# power_stage.net
KiCad netlist of a schematic drawn in Altium Designer
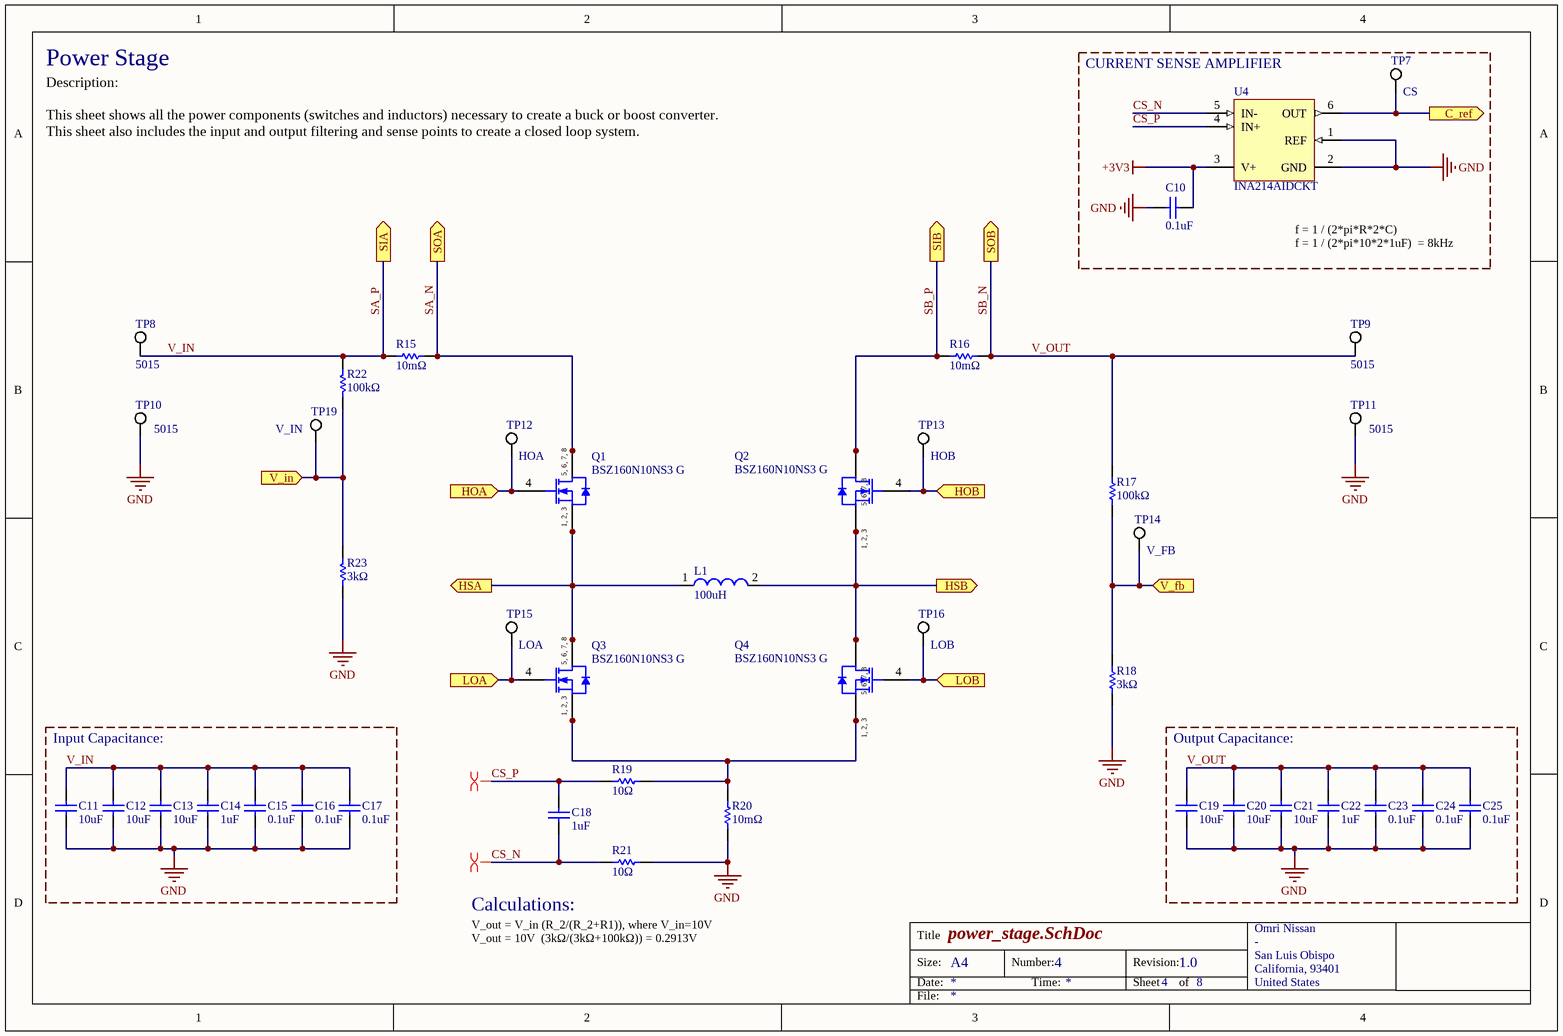
[diagram p0: power_stage.SchDoc]

(export (version "E")
  (design (tool "Eeschema 10.0.6"))
  (components
    (comp (ref "C10")
      (value "0.1uF")
      (footprint "CAPC1608X90X35ML10T15")
      (fields
        (field (name "TOLERANCE") "10%")
        (field (name "VOLTAGE") "50V")
        (field (name "MANUFACTURER") "Murata")
      )
      (libsource (lib "Altium Content Vault") (part "CAP-NP-2"))
    )
    (comp (ref "C11")
      (value "10uF")
      (footprint "CAPC3216X180X20LL20")
      (fields
        (field (name "MANUFACTURER") "TDK")
        (field (name "PCN PART NUMBER") "MLCCPartNumberChange30/Nov/2012")
        (field (name "TOLERANCE") "±10%")
      )
      (libsource (lib "Altium Content Vault") (part "CAP-NP-2"))
    )
    (comp (ref "C12")
      (value "10uF")
      (footprint "CAPC3216X180X20LL20")
      (fields
        (field (name "MANUFACTURER") "TDK")
        (field (name "PCN PART NUMBER") "MLCCPartNumberChange30/Nov/2012")
        (field (name "TOLERANCE") "±10%")
      )
      (libsource (lib "Altium Content Vault") (part "CAP-NP-2"))
    )
    (comp (ref "C13")
      (value "10uF")
      (footprint "CAPC3216X180X20LL20")
      (fields
        (field (name "MANUFACTURER") "TDK")
        (field (name "PCN PART NUMBER") "MLCCPartNumberChange30/Nov/2012")
        (field (name "TOLERANCE") "±10%")
      )
      (libsource (lib "Altium Content Vault") (part "CAP-NP-2"))
    )
    (comp (ref "C14")
      (value "1uF")
      (footprint "CAPC1608X90X20LL10")
      (fields
        (field (name "MANUFACTURER") "TDK")
        (field (name "PCN PART NUMBER") "MLCCPartNumberChange30/Nov/2012")
        (field (name "TOLERANCE") "±10%")
      )
      (libsource (lib "Altium Content Vault") (part "CAP-NP-2"))
    )
    (comp (ref "C15")
      (value "0.1uF")
      (footprint "CAPC1608X90X35ML10T15")
      (fields
        (field (name "TOLERANCE") "10%")
        (field (name "VOLTAGE") "50V")
        (field (name "MANUFACTURER") "Murata")
      )
      (libsource (lib "Altium Content Vault") (part "CAP-NP-2"))
    )
    (comp (ref "C16")
      (value "0.1uF")
      (footprint "CAPC1608X90X35ML10T15")
      (fields
        (field (name "TOLERANCE") "10%")
        (field (name "VOLTAGE") "50V")
        (field (name "MANUFACTURER") "Murata")
      )
      (libsource (lib "Altium Content Vault") (part "CAP-NP-2"))
    )
    (comp (ref "C17")
      (value "0.1uF")
      (footprint "CAPC1608X90X35ML10T15")
      (fields
        (field (name "TOLERANCE") "10%")
        (field (name "VOLTAGE") "50V")
        (field (name "MANUFACTURER") "Murata")
      )
      (libsource (lib "Altium Content Vault") (part "CAP-NP-2"))
    )
    (comp (ref "C18")
      (value "1uF")
      (footprint "CAPC1608X90X20LL10")
      (fields
        (field (name "MANUFACTURER") "TDK")
        (field (name "PCN PART NUMBER") "MLCCPartNumberChange30/Nov/2012")
        (field (name "TOLERANCE") "±10%")
      )
      (libsource (lib "Altium Content Vault") (part "CAP-NP-2"))
    )
    (comp (ref "C19")
      (value "10uF")
      (footprint "CAPC3216X180X20LL20")
      (fields
        (field (name "MANUFACTURER") "TDK")
        (field (name "PCN PART NUMBER") "MLCCPartNumberChange30/Nov/2012")
        (field (name "TOLERANCE") "±10%")
      )
      (libsource (lib "Altium Content Vault") (part "CAP-NP-2"))
    )
    (comp (ref "C20")
      (value "10uF")
      (footprint "CAPC3216X180X20LL20")
      (fields
        (field (name "MANUFACTURER") "TDK")
        (field (name "PCN PART NUMBER") "MLCCPartNumberChange30/Nov/2012")
        (field (name "TOLERANCE") "±10%")
      )
      (libsource (lib "Altium Content Vault") (part "CAP-NP-2"))
    )
    (comp (ref "C21")
      (value "10uF")
      (footprint "CAPC3216X180X20LL20")
      (fields
        (field (name "MANUFACTURER") "TDK")
        (field (name "PCN PART NUMBER") "MLCCPartNumberChange30/Nov/2012")
        (field (name "TOLERANCE") "±10%")
      )
      (libsource (lib "Altium Content Vault") (part "CAP-NP-2"))
    )
    (comp (ref "C22")
      (value "1uF")
      (footprint "CAPC1608X90X20LL10")
      (fields
        (field (name "MANUFACTURER") "TDK")
        (field (name "PCN PART NUMBER") "MLCCPartNumberChange30/Nov/2012")
        (field (name "TOLERANCE") "±10%")
      )
      (libsource (lib "Altium Content Vault") (part "CAP-NP-2"))
    )
    (comp (ref "C23")
      (value "0.1uF")
      (footprint "CAPC1608X90X35ML10T15")
      (fields
        (field (name "TOLERANCE") "10%")
        (field (name "VOLTAGE") "50V")
        (field (name "MANUFACTURER") "Murata")
      )
      (libsource (lib "Altium Content Vault") (part "CAP-NP-2"))
    )
    (comp (ref "C24")
      (value "0.1uF")
      (footprint "CAPC1608X90X35ML10T15")
      (fields
        (field (name "TOLERANCE") "10%")
        (field (name "VOLTAGE") "50V")
        (field (name "MANUFACTURER") "Murata")
      )
      (libsource (lib "Altium Content Vault") (part "CAP-NP-2"))
    )
    (comp (ref "C25")
      (value "0.1uF")
      (footprint "CAPC1608X90X35ML10T15")
      (fields
        (field (name "TOLERANCE") "10%")
        (field (name "VOLTAGE") "50V")
        (field (name "MANUFACTURER") "Murata")
      )
      (libsource (lib "Altium Content Vault") (part "CAP-NP-2"))
    )
    (comp (ref "L1")
      (value "100uH")
      (footprint "WE-PD-XXL")
      (description "7447709101 - SMD-Shielded Power Inductor WE-PD, L = 100 µH")
      (libsource (lib "Altium Content Vault") (part "PAS-IND-INDUCTOR-2"))
    )
    (comp (ref "Q1")
      (value "BSZ160N10NS3 G")
      (footprint "INF-PG-TSDSON-8-1_V")
      (fields (field (name "MANUFACTURER") "Infineon"))
      (libsource (lib "Altium Content Vault") (part "INF-NEMOS-SSSGDDDD-8"))
    )
    (comp (ref "Q2")
      (value "BSZ160N10NS3 G")
      (footprint "INF-PG-TSDSON-8-1_V")
      (fields (field (name "MANUFACTURER") "Infineon"))
      (libsource (lib "Altium Content Vault") (part "INF-NEMOS-SSSGDDDD-8"))
    )
    (comp (ref "Q3")
      (value "BSZ160N10NS3 G")
      (footprint "INF-PG-TSDSON-8-1_V")
      (fields (field (name "MANUFACTURER") "Infineon"))
      (libsource (lib "Altium Content Vault") (part "INF-NEMOS-SSSGDDDD-8"))
    )
    (comp (ref "Q4")
      (value "BSZ160N10NS3 G")
      (footprint "INF-PG-TSDSON-8-1_V")
      (fields (field (name "MANUFACTURER") "Infineon"))
      (libsource (lib "Altium Content Vault") (part "INF-NEMOS-SSSGDDDD-8"))
    )
    (comp (ref "R15")
      (value "10mΩ")
      (footprint "RESC3216X70X50NL05T20")
      (description "ERJ8CWFR010V")
      (fields (field (name "MANUFACTURER") "Panasonic"))
      (libsource (lib "Altium Content Vault") (part "RES"))
    )
    (comp (ref "R16")
      (value "10mΩ")
      (footprint "RESC3216X70X50NL05T20")
      (description "ERJ8CWFR010V")
      (fields (field (name "MANUFACTURER") "Panasonic"))
      (libsource (lib "Altium Content Vault") (part "RES"))
    )
    (comp (ref "R17")
      (value "100kΩ")
      (footprint "RESC1608X55X30ML20T20")
      (description "ERA3AEB104V")
      (fields (field (name "MANUFACTURER") "Panasonic"))
      (libsource (lib "Altium Content Vault") (part "RES"))
    )
    (comp (ref "R18")
      (value "3kΩ")
      (footprint "RESC1608X55X25ML10T15")
      (description "RT0603BRD073KL")
      (fields (field (name "MANUFACTURER") "Yageo"))
      (libsource (lib "Altium Content Vault") (part "RES"))
    )
    (comp (ref "R19")
      (value "10Ω")
      (footprint "RESC1609X50X30NL10T20")
      (description "CRCW060310R0JNEA")
      (fields (field (name "MANUFACTURER") "Vishay Dale"))
      (libsource (lib "Altium Content Vault") (part "RES"))
    )
    (comp (ref "R20")
      (value "10mΩ")
      (footprint "RESC3216X70X50NL05T20")
      (description "ERJ8CWFR010V")
      (fields (field (name "MANUFACTURER") "Panasonic"))
      (libsource (lib "Altium Content Vault") (part "RES"))
    )
    (comp (ref "R21")
      (value "10Ω")
      (footprint "RESC1609X50X30NL10T20")
      (description "CRCW060310R0JNEA")
      (fields (field (name "MANUFACTURER") "Vishay Dale"))
      (libsource (lib "Altium Content Vault") (part "RES"))
    )
    (comp (ref "R22")
      (value "100kΩ")
      (footprint "RESC1608X55X30ML20T20")
      (description "ERA3AEB104V")
      (fields (field (name "MANUFACTURER") "Panasonic"))
      (libsource (lib "Altium Content Vault") (part "RES"))
    )
    (comp (ref "R23")
      (value "3kΩ")
      (footprint "RESC1608X55X25ML10T15")
      (description "RT0603BRD073KL")
      (fields (field (name "MANUFACTURER") "Yageo"))
      (libsource (lib "Altium Content Vault") (part "RES"))
    )
    (comp (ref "TP7")
      (value "CS")
      (footprint "KSTN-5012_V")
      (description "Test Point, White, Through Hole, RoHS, Bulk")
      (fields (field (name "MANUFACTURER") "Keystone"))
      (libsource (lib "Altium Content Vault") (part "TESTPOINT_WHITE"))
    )
    (comp (ref "TP8")
      (value "5015")
      (footprint "KSTN-5015_V")
      (description "Test Point, White, SMT")
      (fields (field (name "MANUFACTURER") "Keystone"))
      (libsource (lib "Altium Content Vault") (part "TESTPOINT_WHITE"))
    )
    (comp (ref "TP9")
      (value "5015")
      (footprint "KSTN-5015_V")
      (description "Test Point, White, SMT")
      (fields (field (name "MANUFACTURER") "Keystone"))
      (libsource (lib "Altium Content Vault") (part "TESTPOINT_WHITE"))
    )
    (comp (ref "TP10")
      (value "5015")
      (footprint "KSTN-5015_V")
      (description "Test Point, White, SMT")
      (fields (field (name "MANUFACTURER") "Keystone"))
      (libsource (lib "Altium Content Vault") (part "TESTPOINT_WHITE"))
    )
    (comp (ref "TP11")
      (value "5015")
      (footprint "KSTN-5015_V")
      (description "Test Point, White, SMT")
      (fields (field (name "MANUFACTURER") "Keystone"))
      (libsource (lib "Altium Content Vault") (part "TESTPOINT_WHITE"))
    )
    (comp (ref "TP12")
      (value "HOA")
      (footprint "KSTN-5012_V")
      (description "Test Point, White, Through Hole, RoHS, Bulk")
      (fields (field (name "MANUFACTURER") "Keystone"))
      (libsource (lib "Altium Content Vault") (part "TESTPOINT_WHITE"))
    )
    (comp (ref "TP13")
      (value "HOB")
      (footprint "KSTN-5012_V")
      (description "Test Point, White, Through Hole, RoHS, Bulk")
      (fields (field (name "MANUFACTURER") "Keystone"))
      (libsource (lib "Altium Content Vault") (part "TESTPOINT_WHITE"))
    )
    (comp (ref "TP14")
      (value "V_FB")
      (footprint "KSTN-5012_V")
      (description "Test Point, White, Through Hole, RoHS, Bulk")
      (fields (field (name "MANUFACTURER") "Keystone"))
      (libsource (lib "Altium Content Vault") (part "TESTPOINT_WHITE"))
    )
    (comp (ref "TP15")
      (value "LOA")
      (footprint "KSTN-5012_V")
      (description "Test Point, White, Through Hole, RoHS, Bulk")
      (fields (field (name "MANUFACTURER") "Keystone"))
      (libsource (lib "Altium Content Vault") (part "TESTPOINT_WHITE"))
    )
    (comp (ref "TP16")
      (value "LOB")
      (footprint "KSTN-5012_V")
      (description "Test Point, White, Through Hole, RoHS, Bulk")
      (fields (field (name "MANUFACTURER") "Keystone"))
      (libsource (lib "Altium Content Vault") (part "TESTPOINT_WHITE"))
    )
    (comp (ref "TP19")
      (value "V_IN")
      (footprint "KSTN-5012_V")
      (description "Test Point, White, Through Hole, RoHS, Bulk")
      (fields (field (name "MANUFACTURER") "Keystone"))
      (libsource (lib "Altium Content Vault") (part "TESTPOINT_WHITE"))
    )
    (comp (ref "U4")
      (value "INA214AIDCKT")
      (footprint "DCK0006A_L")
      (fields (field (name "MANUFACTURER") "TexasInstruments"))
      (libsource (lib "Altium Content Vault") (part "TI-INA21X_199A-DCK-6"))
    )
  )
  (nets
    (net (code "1") (name "+3V3") (class "Default")
      (node (ref "C10") (pin "1") (pinfunction "1_1") (pintype "passive"))
      (node (ref "U4") (pin "3") (pinfunction "V+_3") (pintype "power_in"))
    )
    (net (code "2") (name "/CS_N") (class "Default")
      (node (ref "C18") (pin "2") (pinfunction "2_2") (pintype "passive"))
      (node (ref "R21") (pin "1") (pinfunction "1_1") (pintype "passive"))
      (node (ref "U4") (pin "5") (pinfunction "IN-_5") (pintype "input"))
    )
    (net (code "3") (name "/CS_P") (class "Default")
      (node (ref "C18") (pin "1") (pinfunction "1_1") (pintype "passive"))
      (node (ref "R19") (pin "1") (pinfunction "1_1") (pintype "passive"))
      (node (ref "U4") (pin "4") (pinfunction "IN+_4") (pintype "input"))
    )
    (net (code "4") (name "/C_ref") (class "Default")
      (node (ref "TP7") (pin "1") (pinfunction "1_1") (pintype "passive"))
      (node (ref "U4") (pin "6") (pinfunction "OUT_6") (pintype "output"))
    )
    (net (code "5") (name "/HOA") (class "Default")
      (node (ref "Q1") (pin "4") (pinfunction "GATE_4") (pintype "passive"))
      (node (ref "TP12") (pin "1") (pinfunction "1_1") (pintype "passive"))
    )
    (net (code "6") (name "/HOB") (class "Default")
      (node (ref "Q2") (pin "4") (pinfunction "GATE_4") (pintype "passive"))
      (node (ref "TP13") (pin "1") (pinfunction "1_1") (pintype "passive"))
    )
    (net (code "7") (name "/HSA") (class "Default")
      (node (ref "L1") (pin "1") (pinfunction "1_1") (pintype "passive"))
      (node (ref "Q1") (pin "1") (pinfunction "SOURCE_1") (pintype "passive"))
      (node (ref "Q1") (pin "2") (pinfunction "SOURCE_2") (pintype "passive"))
      (node (ref "Q1") (pin "3") (pinfunction "SOURCE_3") (pintype "passive"))
      (node (ref "Q3") (pin "5") (pinfunction "DRAIN_5") (pintype "passive"))
      (node (ref "Q3") (pin "6") (pinfunction "DRAIN_6") (pintype "passive"))
      (node (ref "Q3") (pin "7") (pinfunction "DRAIN_7") (pintype "passive"))
      (node (ref "Q3") (pin "8") (pinfunction "DRAIN_8") (pintype "passive"))
    )
    (net (code "8") (name "/HSB") (class "Default")
      (node (ref "L1") (pin "2") (pinfunction "2_2") (pintype "passive"))
      (node (ref "Q2") (pin "1") (pinfunction "SOURCE_1") (pintype "passive"))
      (node (ref "Q2") (pin "2") (pinfunction "SOURCE_2") (pintype "passive"))
      (node (ref "Q2") (pin "3") (pinfunction "SOURCE_3") (pintype "passive"))
      (node (ref "Q4") (pin "5") (pinfunction "DRAIN_5") (pintype "passive"))
      (node (ref "Q4") (pin "6") (pinfunction "DRAIN_6") (pintype "passive"))
      (node (ref "Q4") (pin "7") (pinfunction "DRAIN_7") (pintype "passive"))
      (node (ref "Q4") (pin "8") (pinfunction "DRAIN_8") (pintype "passive"))
    )
    (net (code "9") (name "/LOA") (class "Default")
      (node (ref "Q3") (pin "4") (pinfunction "GATE_4") (pintype "passive"))
      (node (ref "TP15") (pin "1") (pinfunction "1_1") (pintype "passive"))
    )
    (net (code "10") (name "/LOB") (class "Default")
      (node (ref "Q4") (pin "4") (pinfunction "GATE_4") (pintype "passive"))
      (node (ref "TP16") (pin "1") (pinfunction "1_1") (pintype "passive"))
    )
    (net (code "11") (name "/SA_N") (class "Default")
      (node (ref "Q1") (pin "5") (pinfunction "DRAIN_5") (pintype "passive"))
      (node (ref "Q1") (pin "6") (pinfunction "DRAIN_6") (pintype "passive"))
      (node (ref "Q1") (pin "7") (pinfunction "DRAIN_7") (pintype "passive"))
      (node (ref "Q1") (pin "8") (pinfunction "DRAIN_8") (pintype "passive"))
      (node (ref "R15") (pin "2") (pinfunction "2_2") (pintype "passive"))
    )
    (net (code "12") (name "/SA_P") (class "Default")
      (node (ref "C11") (pin "2") (pinfunction "2_2") (pintype "passive"))
      (node (ref "C12") (pin "2") (pinfunction "2_2") (pintype "passive"))
      (node (ref "C13") (pin "2") (pinfunction "2_2") (pintype "passive"))
      (node (ref "C14") (pin "1") (pinfunction "1_1") (pintype "passive"))
      (node (ref "C15") (pin "2") (pinfunction "2_2") (pintype "passive"))
      (node (ref "C16") (pin "2") (pinfunction "2_2") (pintype "passive"))
      (node (ref "C17") (pin "2") (pinfunction "2_2") (pintype "passive"))
      (node (ref "R15") (pin "1") (pinfunction "1_1") (pintype "passive"))
      (node (ref "R22") (pin "2") (pinfunction "2_2") (pintype "passive"))
      (node (ref "TP8") (pin "1") (pinfunction "1_1") (pintype "passive"))
    )
    (net (code "13") (name "/SB_N") (class "Default")
      (node (ref "C19") (pin "2") (pinfunction "2_2") (pintype "passive"))
      (node (ref "C20") (pin "2") (pinfunction "2_2") (pintype "passive"))
      (node (ref "C21") (pin "2") (pinfunction "2_2") (pintype "passive"))
      (node (ref "C22") (pin "1") (pinfunction "1_1") (pintype "passive"))
      (node (ref "C23") (pin "2") (pinfunction "2_2") (pintype "passive"))
      (node (ref "C24") (pin "2") (pinfunction "2_2") (pintype "passive"))
      (node (ref "C25") (pin "2") (pinfunction "2_2") (pintype "passive"))
      (node (ref "R16") (pin "2") (pinfunction "2_2") (pintype "passive"))
      (node (ref "R17") (pin "2") (pinfunction "2_2") (pintype "passive"))
      (node (ref "TP9") (pin "1") (pinfunction "1_1") (pintype "passive"))
    )
    (net (code "14") (name "/SB_P") (class "Default")
      (node (ref "Q2") (pin "5") (pinfunction "DRAIN_5") (pintype "passive"))
      (node (ref "Q2") (pin "6") (pinfunction "DRAIN_6") (pintype "passive"))
      (node (ref "Q2") (pin "7") (pinfunction "DRAIN_7") (pintype "passive"))
      (node (ref "Q2") (pin "8") (pinfunction "DRAIN_8") (pintype "passive"))
      (node (ref "R16") (pin "1") (pinfunction "1_1") (pintype "passive"))
    )
    (net (code "15") (name "/V_fb") (class "Default")
      (node (ref "R17") (pin "1") (pinfunction "1_1") (pintype "passive"))
      (node (ref "R18") (pin "2") (pinfunction "2_2") (pintype "passive"))
      (node (ref "TP14") (pin "1") (pinfunction "1_1") (pintype "passive"))
    )
    (net (code "16") (name "/V_in") (class "Default")
      (node (ref "R22") (pin "1") (pinfunction "1_1") (pintype "passive"))
      (node (ref "R23") (pin "2") (pinfunction "2_2") (pintype "passive"))
      (node (ref "TP19") (pin "1") (pinfunction "1_1") (pintype "passive"))
    )
    (net (code "17") (name "GND") (class "Default")
      (node (ref "C10") (pin "2") (pinfunction "2_2") (pintype "passive"))
      (node (ref "C11") (pin "1") (pinfunction "1_1") (pintype "passive"))
      (node (ref "C12") (pin "1") (pinfunction "1_1") (pintype "passive"))
      (node (ref "C13") (pin "1") (pinfunction "1_1") (pintype "passive"))
      (node (ref "C14") (pin "2") (pinfunction "2_2") (pintype "passive"))
      (node (ref "C15") (pin "1") (pinfunction "1_1") (pintype "passive"))
      (node (ref "C16") (pin "1") (pinfunction "1_1") (pintype "passive"))
      (node (ref "C17") (pin "1") (pinfunction "1_1") (pintype "passive"))
      (node (ref "C19") (pin "1") (pinfunction "1_1") (pintype "passive"))
      (node (ref "C20") (pin "1") (pinfunction "1_1") (pintype "passive"))
      (node (ref "C21") (pin "1") (pinfunction "1_1") (pintype "passive"))
      (node (ref "C22") (pin "2") (pinfunction "2_2") (pintype "passive"))
      (node (ref "C23") (pin "1") (pinfunction "1_1") (pintype "passive"))
      (node (ref "C24") (pin "1") (pinfunction "1_1") (pintype "passive"))
      (node (ref "C25") (pin "1") (pinfunction "1_1") (pintype "passive"))
      (node (ref "R18") (pin "1") (pinfunction "1_1") (pintype "passive"))
      (node (ref "R20") (pin "1") (pinfunction "1_1") (pintype "passive"))
      (node (ref "R21") (pin "2") (pinfunction "2_2") (pintype "passive"))
      (node (ref "R23") (pin "1") (pinfunction "1_1") (pintype "passive"))
      (node (ref "TP10") (pin "1") (pinfunction "1_1") (pintype "passive"))
      (node (ref "TP11") (pin "1") (pinfunction "1_1") (pintype "passive"))
      (node (ref "U4") (pin "1") (pinfunction "REF_1") (pintype "input"))
      (node (ref "U4") (pin "2") (pinfunction "GND_2") (pintype "power_in"))
    )
    (net (code "18") (name "Net-(Q3-SOURCE-Pad1)") (class "Default")
      (node (ref "Q3") (pin "1") (pinfunction "SOURCE_1") (pintype "passive"))
      (node (ref "Q3") (pin "2") (pinfunction "SOURCE_2") (pintype "passive"))
      (node (ref "Q3") (pin "3") (pinfunction "SOURCE_3") (pintype "passive"))
      (node (ref "Q4") (pin "1") (pinfunction "SOURCE_1") (pintype "passive"))
      (node (ref "Q4") (pin "2") (pinfunction "SOURCE_2") (pintype "passive"))
      (node (ref "Q4") (pin "3") (pinfunction "SOURCE_3") (pintype "passive"))
      (node (ref "R19") (pin "2") (pinfunction "2_2") (pintype "passive"))
      (node (ref "R20") (pin "2") (pinfunction "2_2") (pintype "passive"))
    )
  )
)
